# JTAG.net
KiCad netlist of a schematic drawn in Altium Designer
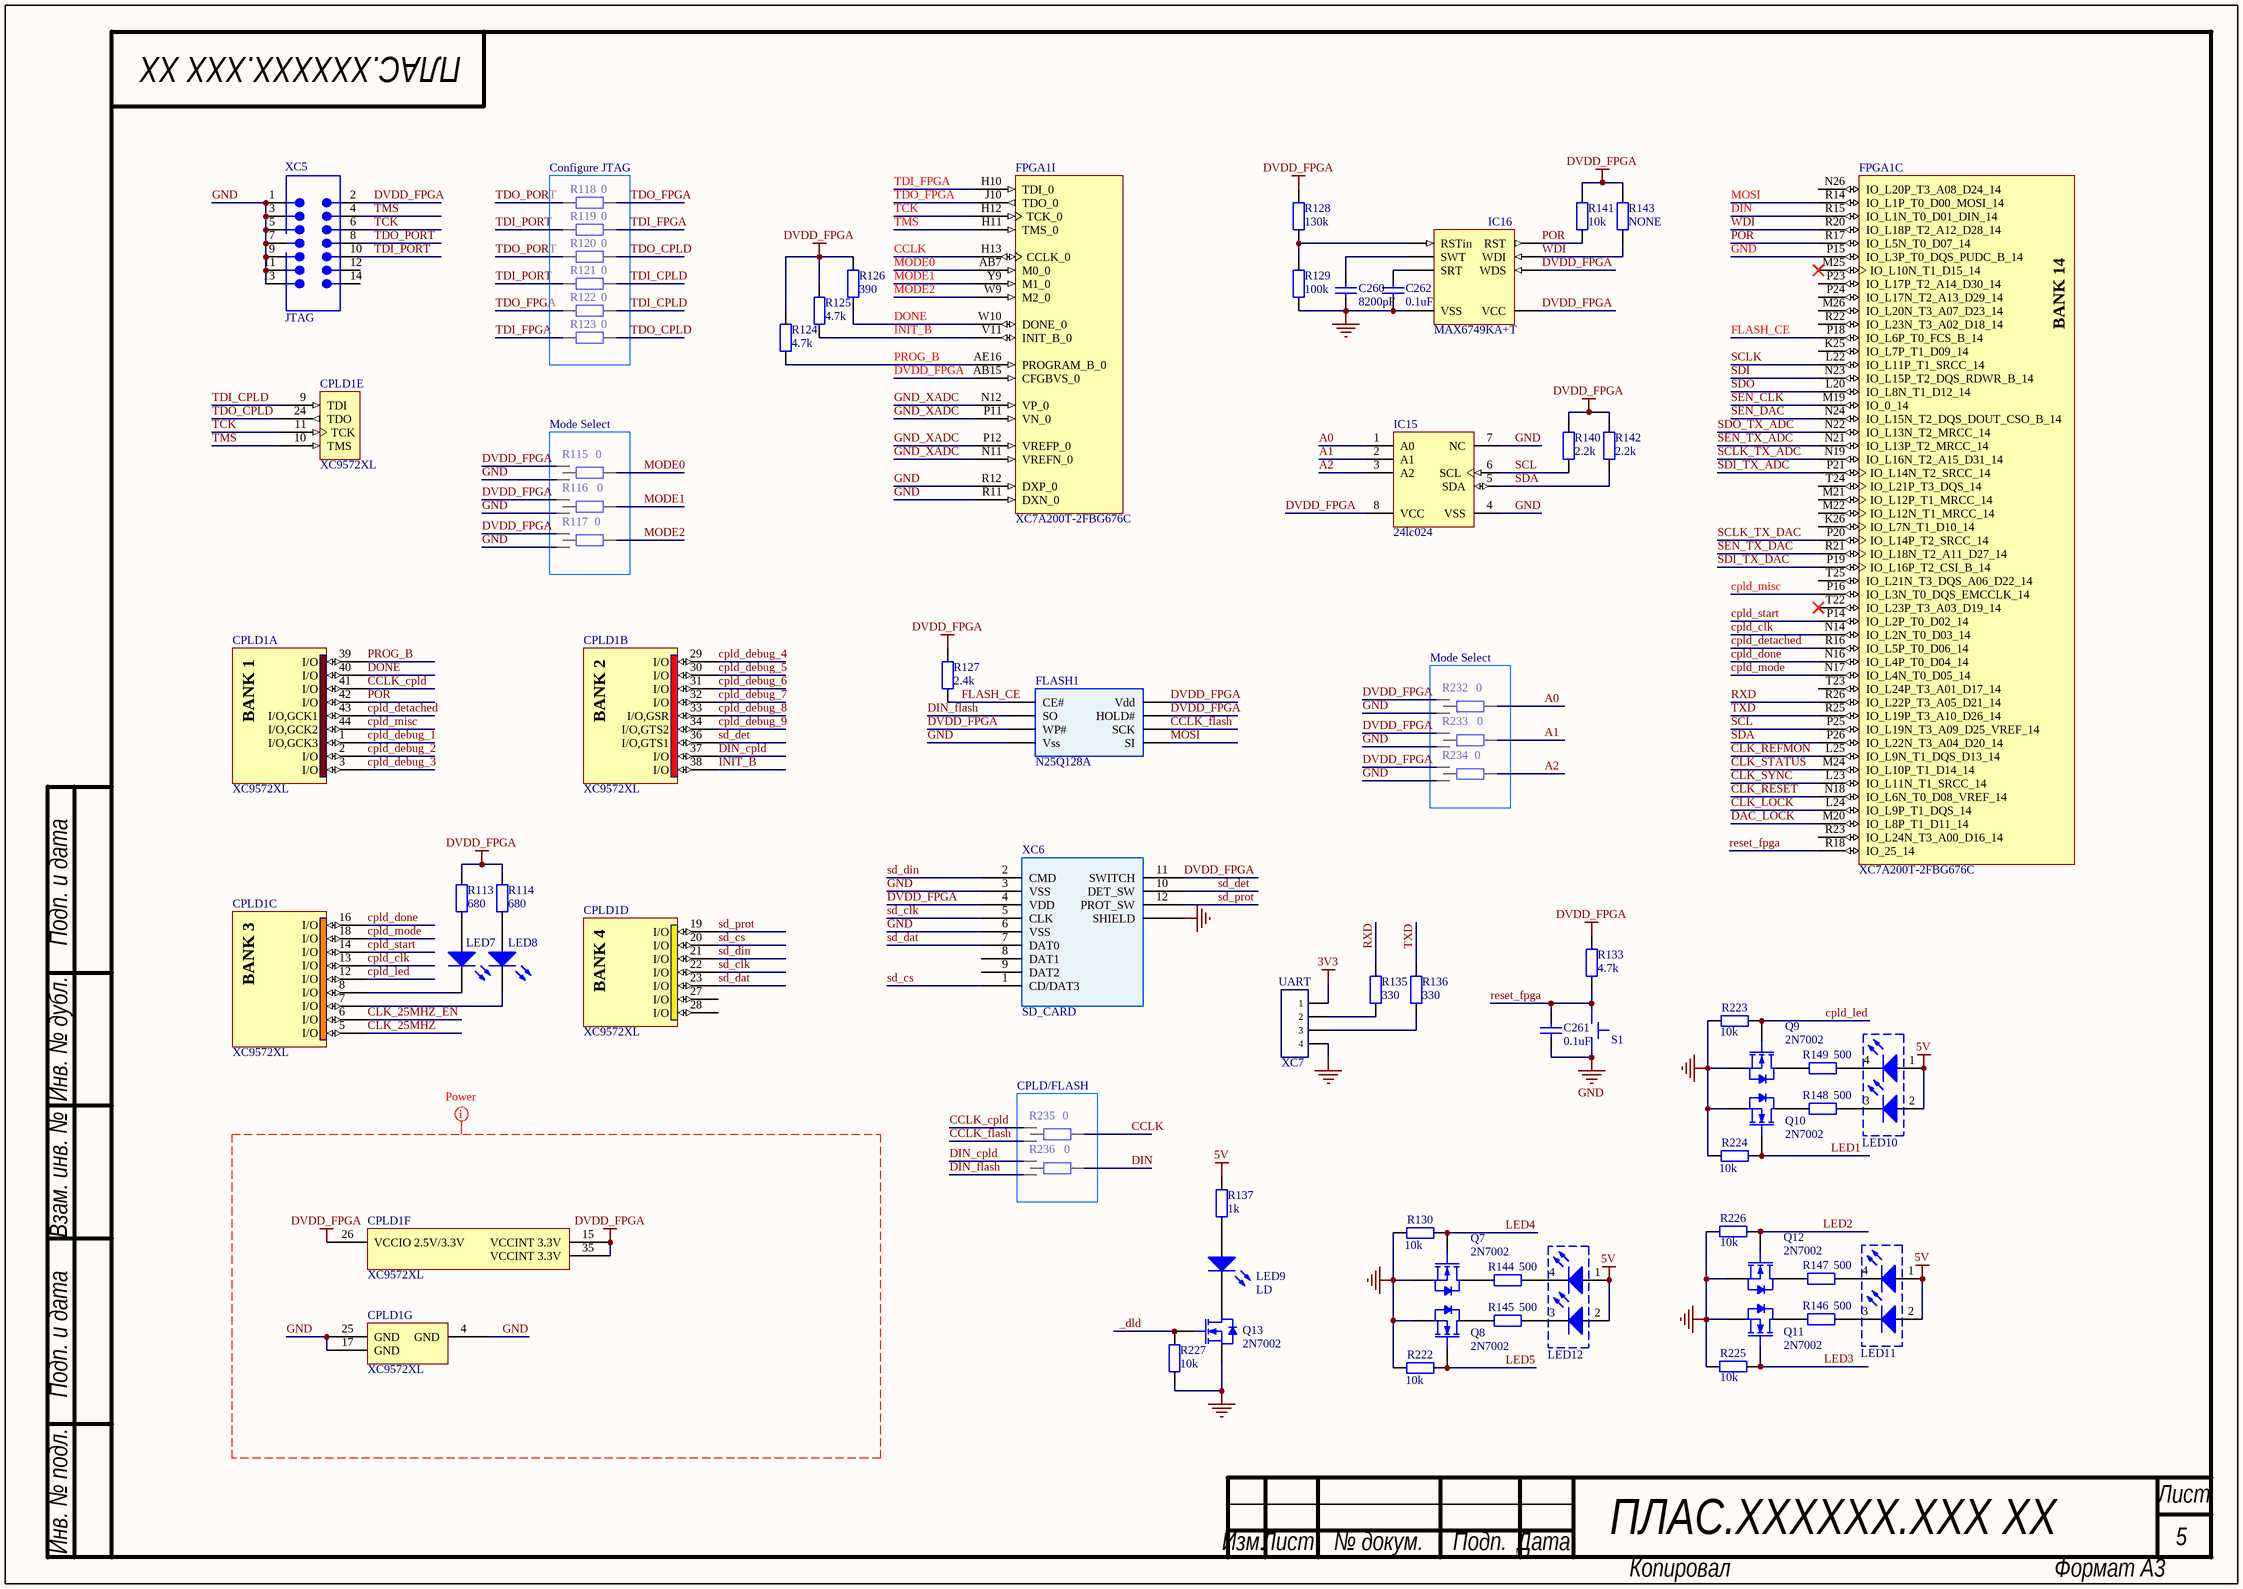
[diagram p0: JTAG.SchDoc]

(export (version "E")
  (design (tool "Eeschema 10.0.6"))
  (components
    (comp (ref "C260")
      (value "8200pF")
      (footprint "C0603")
      (description "Cer Cap Small")
      (fields (field (name "MANUFACTURER") "Murata") (field (name "VOLTAGE") "50V"))
      (libsource (lib "") (part "Cer Cap_1"))
    )
    (comp (ref "C261")
      (value "0.1uF")
      (footprint "C0603")
      (description "Cer Cap Small")
      (fields (field (name "MANUFACTURER") "Murata") (field (name "VOLTAGE") "16V"))
      (libsource (lib "USRP2_Clone") (part "Cer Cap"))
    )
    (comp (ref "C262")
      (value "0.1uF")
      (footprint "C0603")
      (description "Cer Cap Small")
      (fields (field (name "MANUFACTURER") "Murata") (field (name "VOLTAGE") "16V"))
      (libsource (lib "") (part "Cer Cap_1"))
    )
    (comp (ref "CPLD1")
      (value "XC9572XL")
      (footprint "VQFP44")
      (fields (field (name "VOLTAGE") "3.3 V"))
      (libsource (lib "USRP2_Clone") (part "XC9572XL-10VQ44C"))
    )
    (comp (ref "FLASH1")
      (value "N25Q128A")
      (footprint "SOIC8-W")
      (description "SPI Flash")
      (fields (field (name "VOLTAGE") "2.7-3.6V") (field (name "MANUFACTURER") "Micron Technology"))
      (libsource (lib "USRP2_Clone") (part "SST25VF016B-xx-xx-S2Ax"))
    )
    (comp (ref "FPGA1")
      (value "XC7A200T-2FBG676C")
      (footprint "FGG676")
      (description "Artix-7 FPGA, 400 User I/Os, 8 GTP, 676-Ball BGA, Speed Grade 2, Commercial Grade, Pb-Free")
      (fields (field (name "GENERIC PART NUMBER") "XC7A200T") (field (name "MANUFACTURER") "Xilinx"))
      (libsource (lib "USRP2_Clone") (part "XC7A200T-2FBG676C"))
    )
    (comp (ref "IC15")
      (value "24lc024")
      (footprint "SOIC_SN8")
      (description "I2C EEPROM")
      (fields (field (name "VOLTAGE") "2.5-5.5V") (field (name "MANUFACTURER") "Microchip"))
      (libsource (lib "USRP2_Clone") (part "24lc024"))
    )
    (comp (ref "IC16")
      (value "MAX6749KA+T")
      (footprint "SOT-23-8")
      (description "uC Reset Circuits")
      (fields (field (name "VOLTAGE") "1.0-5.5V") (field (name "MANUFACTURER") "Maxim"))
      (libsource (lib "USRP2_Clone") (part "MAX6749KA+T"))
    )
    (comp (ref "LED7")
      (value "LED")
      (footprint "LED_0402_Blue")
      (description "Typical RED, GREEN, YELLOW, AMBER GaAs LED")
      (fields (field (name "MANUFACTURER") "Kingbright"))
      (libsource (lib "USRP2_Clone") (part "LED"))
    )
    (comp (ref "LED8")
      (value "LED")
      (footprint "LED_0402_Blue")
      (description "Typical RED, GREEN, YELLOW, AMBER GaAs LED")
      (fields (field (name "MANUFACTURER") "Kingbright"))
      (libsource (lib "USRP2_Clone") (part "LED"))
    )
    (comp (ref "LED9")
      (value "LD")
      (footprint "LED_0402_Blue")
      (description "Typical RED, GREEN, YELLOW, AMBER GaAs LED")
      (fields (field (name "MANUFACTURER") "Kingbright"))
      (libsource (lib "USRP2_Clone") (part "LED"))
    )
    (comp (ref "LED10")
      (value "Green")
      (footprint "LED_PACK")
      (description "LED Pack For Front Panel")
      (fields (field (name "MANUFACTURER") "Kingbright"))
      (libsource (lib "USRP2_Clone") (part "LED_PACK"))
    )
    (comp (ref "LED11")
      (value "Green")
      (footprint "LED_PACK")
      (description "LED Pack For Front Panel")
      (fields (field (name "MANUFACTURER") "Kingbright"))
      (libsource (lib "USRP2_Clone") (part "LED_PACK"))
    )
    (comp (ref "LED12")
      (value "Green")
      (footprint "LED_PACK")
      (description "LED Pack For Front Panel")
      (fields (field (name "MANUFACTURER") "Kingbright"))
      (libsource (lib "USRP2_Clone") (part "LED_PACK"))
    )
    (comp (ref "Q7")
      (value "2N7002")
      (footprint "SOT-23")
      (description "N-Channel MOSFET 2N7002")
      (fields (field (name "VOLTAGE") "60V"))
      (libsource (lib "USRP2_Clone") (part "2N7002"))
    )
    (comp (ref "Q8")
      (value "2N7002")
      (footprint "SOT-23")
      (description "N-Channel MOSFET 2N7002")
      (fields (field (name "VOLTAGE") "60V"))
      (libsource (lib "USRP2_Clone") (part "2N7002"))
    )
    (comp (ref "Q9")
      (value "2N7002")
      (footprint "SOT-23")
      (description "N-Channel MOSFET 2N7002")
      (fields (field (name "VOLTAGE") "60V"))
      (libsource (lib "USRP2_Clone") (part "2N7002"))
    )
    (comp (ref "Q10")
      (value "2N7002")
      (footprint "SOT-23")
      (description "N-Channel MOSFET 2N7002")
      (fields (field (name "VOLTAGE") "60V"))
      (libsource (lib "USRP2_Clone") (part "2N7002"))
    )
    (comp (ref "Q11")
      (value "2N7002")
      (footprint "SOT-23")
      (description "N-Channel MOSFET 2N7002")
      (fields (field (name "VOLTAGE") "60V"))
      (libsource (lib "USRP2_Clone") (part "2N7002"))
    )
    (comp (ref "Q12")
      (value "2N7002")
      (footprint "SOT-23")
      (description "N-Channel MOSFET 2N7002")
      (fields (field (name "VOLTAGE") "60V"))
      (libsource (lib "USRP2_Clone") (part "2N7002"))
    )
    (comp (ref "Q13")
      (value "2N7002")
      (footprint "SOT-23")
      (description "N-Channel MOSFET 2N7002")
      (fields (field (name "VOLTAGE") "60V"))
      (libsource (lib "USRP2_Clone") (part "2N7002"))
    )
    (comp (ref "R113")
      (value "680")
      (footprint "R0402")
      (description "Resistor")
      (fields (field (name "TOLERANCE") "5%") (field (name "POWER") "0.062 Wt"))
      (libsource (lib "") (part "Res_2"))
    )
    (comp (ref "R114")
      (value "680")
      (footprint "R0402")
      (description "Resistor")
      (fields (field (name "TOLERANCE") "5%") (field (name "POWER") "0.062 Wt"))
      (libsource (lib "") (part "Res_2"))
    )
    (comp (ref "R115")
      (value "0")
      (footprint "R0402_Switch")
      (description "Resistor")
      (fields (field (name "TOLERANCE") "5%") (field (name "POWER") "0.062 Wt"))
      (libsource (lib "USRP2_Clone") (part "Res_Switch"))
    )
    (comp (ref "R116")
      (value "0")
      (footprint "R0402_Switch")
      (description "Resistor")
      (fields (field (name "TOLERANCE") "5%") (field (name "POWER") "0.062 Wt"))
      (libsource (lib "USRP2_Clone") (part "Res_Switch"))
    )
    (comp (ref "R117")
      (value "0")
      (footprint "R0402_Switch")
      (description "Resistor")
      (fields (field (name "TOLERANCE") "5%") (field (name "POWER") "0.062 Wt"))
      (libsource (lib "USRP2_Clone") (part "Res_Switch"))
    )
    (comp (ref "R118")
      (value "0")
      (footprint "R0402")
      (description "Resistor")
      (fields (field (name "TOLERANCE") "5%") (field (name "POWER") "0.062 Wt"))
      (libsource (lib "") (part "Res_1"))
    )
    (comp (ref "R119")
      (value "0")
      (footprint "R0402")
      (description "Resistor")
      (fields (field (name "TOLERANCE") "5%") (field (name "POWER") "0.062 Wt"))
      (libsource (lib "") (part "Res_1"))
    )
    (comp (ref "R120")
      (value "0")
      (footprint "R0402")
      (description "Resistor")
      (fields (field (name "TOLERANCE") "5%") (field (name "POWER") "0.062 Wt"))
      (libsource (lib "") (part "Res_1"))
    )
    (comp (ref "R121")
      (value "0")
      (footprint "R0402")
      (description "Resistor")
      (fields (field (name "TOLERANCE") "5%") (field (name "POWER") "0.062 Wt"))
      (libsource (lib "") (part "Res_1"))
    )
    (comp (ref "R122")
      (value "0")
      (footprint "R0402")
      (description "Resistor")
      (fields (field (name "TOLERANCE") "5%") (field (name "POWER") "0.062 Wt"))
      (libsource (lib "") (part "Res_1"))
    )
    (comp (ref "R123")
      (value "0")
      (footprint "R0402")
      (description "Resistor")
      (fields (field (name "TOLERANCE") "5%") (field (name "POWER") "0.062 Wt"))
      (libsource (lib "") (part "Res_1"))
    )
    (comp (ref "R124")
      (value "4.7k")
      (footprint "R0402")
      (description "Resistor")
      (fields (field (name "TOLERANCE") "5%") (field (name "POWER") "0.062 Wt"))
      (libsource (lib "USRP2_Clone") (part "Res"))
    )
    (comp (ref "R125")
      (value "4.7k")
      (footprint "R0402")
      (description "Resistor")
      (fields (field (name "TOLERANCE") "5%") (field (name "POWER") "0.062 Wt"))
      (libsource (lib "") (part "Res_6"))
    )
    (comp (ref "R126")
      (value "390")
      (footprint "R0402")
      (description "Resistor")
      (fields (field (name "TOLERANCE") "5%") (field (name "POWER") "0.062 Wt"))
      (libsource (lib "USRP2_Clone") (part "Res"))
    )
    (comp (ref "R127")
      (value "2.4k")
      (footprint "R0402")
      (description "Resistor")
      (fields (field (name "TOLERANCE") "5%") (field (name "POWER") "0.062 Wt"))
      (libsource (lib "USRP2_Clone") (part "Res"))
    )
    (comp (ref "R128")
      (value "130k")
      (footprint "R0402")
      (description "Resistor")
      (fields (field (name "TOLERANCE") "5%") (field (name "POWER") "0.062 Wt"))
      (libsource (lib "") (part "Res_2"))
    )
    (comp (ref "R129")
      (value "100k")
      (footprint "R0402")
      (description "Resistor")
      (fields (field (name "TOLERANCE") "5%") (field (name "POWER") "0.062 Wt"))
      (libsource (lib "") (part "Res_2"))
    )
    (comp (ref "R130")
      (value "10k")
      (footprint "R0402")
      (description "Resistor")
      (fields (field (name "TOLERANCE") "5%") (field (name "POWER") "0.062 Wt"))
      (libsource (lib "") (part "Res_3"))
    )
    (comp (ref "R133")
      (value "4.7k")
      (footprint "R0402")
      (description "Resistor")
      (fields (field (name "TOLERANCE") "5%") (field (name "POWER") "0.062 Wt"))
      (libsource (lib "") (part "Res_2"))
    )
    (comp (ref "R135")
      (value "330")
      (footprint "R0402")
      (description "Resistor")
      (fields (field (name "TOLERANCE") "5%") (field (name "POWER") "0.062 Wt"))
      (libsource (lib "") (part "Res_4"))
    )
    (comp (ref "R136")
      (value "330")
      (footprint "R0402")
      (description "Resistor")
      (fields (field (name "TOLERANCE") "5%") (field (name "POWER") "0.062 Wt"))
      (libsource (lib "") (part "Res_4"))
    )
    (comp (ref "R137")
      (value "1k")
      (footprint "R0402")
      (description "Resistor")
      (fields (field (name "TOLERANCE") "5%") (field (name "POWER") "0.062 Wt"))
      (libsource (lib "") (part "Res_2"))
    )
    (comp (ref "R140")
      (value "2.2k")
      (footprint "R0402")
      (description "Resistor")
      (fields (field (name "TOLERANCE") "5%") (field (name "POWER") "0.062 Wt"))
      (libsource (lib "") (part "Res_2"))
    )
    (comp (ref "R141")
      (value "10k")
      (footprint "R0402")
      (description "Resistor")
      (fields (field (name "TOLERANCE") "5%") (field (name "POWER") "0.062 Wt"))
      (libsource (lib "") (part "Res_2"))
    )
    (comp (ref "R142")
      (value "2.2k")
      (footprint "R0402")
      (description "Resistor")
      (fields (field (name "TOLERANCE") "5%") (field (name "POWER") "0.062 Wt"))
      (libsource (lib "") (part "Res_2"))
    )
    (comp (ref "R143")
      (value "NONE")
      (footprint "R0402")
      (description "Resistor")
      (fields (field (name "TOLERANCE") "5%") (field (name "POWER") "0.062 Wt"))
      (libsource (lib "") (part "Res_2"))
    )
    (comp (ref "R144")
      (value "500")
      (footprint "R0402")
      (description "Resistor")
      (fields (field (name "TOLERANCE") "5%") (field (name "POWER") "0.062 Wt"))
      (libsource (lib "") (part "Res_5"))
    )
    (comp (ref "R145")
      (value "500")
      (footprint "R0402")
      (description "Resistor")
      (fields (field (name "TOLERANCE") "5%") (field (name "POWER") "0.062 Wt"))
      (libsource (lib "") (part "Res_5"))
    )
    (comp (ref "R146")
      (value "500")
      (footprint "R0402")
      (description "Resistor")
      (fields (field (name "TOLERANCE") "5%") (field (name "POWER") "0.062 Wt"))
      (libsource (lib "") (part "Res_2"))
    )
    (comp (ref "R147")
      (value "500")
      (footprint "R0402")
      (description "Resistor")
      (fields (field (name "TOLERANCE") "5%") (field (name "POWER") "0.062 Wt"))
      (libsource (lib "") (part "Res_2"))
    )
    (comp (ref "R148")
      (value "500")
      (footprint "R0402")
      (description "Resistor")
      (fields (field (name "TOLERANCE") "5%") (field (name "POWER") "0.062 Wt"))
      (libsource (lib "") (part "Res_1"))
    )
    (comp (ref "R149")
      (value "500")
      (footprint "R0402")
      (description "Resistor")
      (fields (field (name "TOLERANCE") "5%") (field (name "POWER") "0.062 Wt"))
      (libsource (lib "") (part "Res_5"))
    )
    (comp (ref "R222")
      (value "10k")
      (footprint "R0402")
      (description "Resistor")
      (fields (field (name "TOLERANCE") "5%") (field (name "POWER") "0.062 Wt"))
      (libsource (lib "") (part "Res_3"))
    )
    (comp (ref "R223")
      (value "10k")
      (footprint "R0402")
      (description "Resistor")
      (fields (field (name "TOLERANCE") "5%") (field (name "POWER") "0.062 Wt"))
      (libsource (lib "") (part "Res_3"))
    )
    (comp (ref "R224")
      (value "10k")
      (footprint "R0402")
      (description "Resistor")
      (fields (field (name "TOLERANCE") "5%") (field (name "POWER") "0.062 Wt"))
      (libsource (lib "") (part "Res_3"))
    )
    (comp (ref "R225")
      (value "10k")
      (footprint "R0402")
      (description "Resistor")
      (fields (field (name "TOLERANCE") "5%") (field (name "POWER") "0.062 Wt"))
      (libsource (lib "") (part "Res_4"))
    )
    (comp (ref "R226")
      (value "10k")
      (footprint "R0402")
      (description "Resistor")
      (fields (field (name "TOLERANCE") "5%") (field (name "POWER") "0.062 Wt"))
      (libsource (lib "") (part "Res_4"))
    )
    (comp (ref "R227")
      (value "10k")
      (footprint "R0402")
      (description "Resistor")
      (fields (field (name "TOLERANCE") "5%") (field (name "POWER") "0.062 Wt"))
      (libsource (lib "") (part "Res_2"))
    )
    (comp (ref "R232")
      (value "0")
      (footprint "R0402_Switch")
      (description "Resistor")
      (fields (field (name "TOLERANCE") "5%") (field (name "POWER") "0.062 Wt"))
      (libsource (lib "USRP2_Clone") (part "Res_Switch"))
    )
    (comp (ref "R233")
      (value "0")
      (footprint "R0402_Switch")
      (description "Resistor")
      (fields (field (name "TOLERANCE") "5%") (field (name "POWER") "0.062 Wt"))
      (libsource (lib "USRP2_Clone") (part "Res_Switch"))
    )
    (comp (ref "R234")
      (value "0")
      (footprint "R0402_Switch")
      (description "Resistor")
      (fields (field (name "TOLERANCE") "5%") (field (name "POWER") "0.062 Wt"))
      (libsource (lib "USRP2_Clone") (part "Res_Switch"))
    )
    (comp (ref "R235")
      (value "0")
      (footprint "R0402_Switch")
      (description "Resistor")
      (fields (field (name "TOLERANCE") "5%") (field (name "POWER") "0.062 Wt"))
      (libsource (lib "USRP2_Clone") (part "Res_Switch"))
    )
    (comp (ref "R236")
      (value "0")
      (footprint "R0402_Switch")
      (description "Resistor")
      (fields (field (name "TOLERANCE") "5%") (field (name "POWER") "0.062 Wt"))
      (libsource (lib "USRP2_Clone") (part "Res_Switch"))
    )
    (comp (ref "S1")
      (value "RST_FPGA")
      (footprint "B3FS-1000")
      (fields (field (name "MANUFACTURER") "Omron") (field (name "VOLTAGE") "24V"))
      (libsource (lib "USRP2_Clone") (part "Push Button"))
    )
    (comp (ref "XC5")
      (value "JTAG")
      (footprint "JTAG Mail")
      (description "Male Header JTAG")
      (fields (field (name "MANUFACTURER") "CNC Tech"))
      (libsource (lib "USRP2_Clone") (part "JTAG Male"))
    )
    (comp (ref "XC6")
      (value "SD_CARD")
      (footprint "SD_Card")
      (fields (field (name "MANUFACTURER") "Tyco Electronics"))
      (libsource (lib "USRP2_Clone") (part "SD_Card"))
    )
    (comp (ref "XC7")
      (value "UART")
      (footprint "Right Angle Male Header")
      (description "4-Way Angle PCB Header")
      (libsource (lib "USRP2_Clone") (part "4-Way Header"))
    )
  )
  (nets
    (net (code "1") (name "/A0") (class "Default")
      (node (ref "IC15") (pin "1") (pinfunction "A0_1") (pintype "passive"))
      (node (ref "R232") (pin "2") (pinfunction "2_2") (pintype "passive"))
    )
    (net (code "2") (name "/A1") (class "Default")
      (node (ref "IC15") (pin "2") (pinfunction "A1_2") (pintype "passive"))
      (node (ref "R233") (pin "2") (pinfunction "2_2") (pintype "passive"))
    )
    (net (code "3") (name "/A2") (class "Default")
      (node (ref "IC15") (pin "3") (pinfunction "A2_3") (pintype "passive"))
      (node (ref "R234") (pin "2") (pinfunction "2_2") (pintype "passive"))
    )
    (net (code "4") (name "/CCLK") (class "Default")
      (node (ref "FPGA1") (pin "H13") (pinfunction "CCLK_0_H13") (pintype "bidirectional"))
      (node (ref "R235") (pin "2") (pinfunction "2_2") (pintype "passive"))
    )
    (net (code "5") (name "/CCLK_cpld") (class "Default")
      (node (ref "CPLD1") (pin "41") (pinfunction "I/O_41") (pintype "bidirectional"))
      (node (ref "R235") (pin "1") (pinfunction "1_1") (pintype "passive"))
    )
    (net (code "6") (name "/CCLK_flash") (class "Default")
      (node (ref "FLASH1") (pin "6") (pinfunction "SCK_6") (pintype "passive"))
      (node (ref "R235") (pin "3") (pinfunction "3_3") (pintype "passive"))
    )
    (net (code "7") (name "/CLK_25MHZ") (class "Default")
      (node (ref "CPLD1") (pin "5") (pinfunction "I/O_5") (pintype "bidirectional"))
    )
    (net (code "8") (name "/CLK_25MHZ_EN") (class "Default")
      (node (ref "CPLD1") (pin "6") (pinfunction "I/O_6") (pintype "bidirectional"))
    )
    (net (code "9") (name "/CLK_LOCK") (class "Default")
      (node (ref "FPGA1") (pin "L24") (pinfunction "IO_L9P_T1_DQS_14_L24") (pintype "bidirectional"))
    )
    (net (code "10") (name "/CLK_REFMON") (class "Default")
      (node (ref "FPGA1") (pin "L25") (pinfunction "IO_L9N_T1_DQS_D13_14_L25") (pintype "bidirectional"))
    )
    (net (code "11") (name "/CLK_RESET") (class "Default")
      (node (ref "FPGA1") (pin "N18") (pinfunction "IO_L6N_T0_D08_VREF_14_N18") (pintype "bidirectional"))
    )
    (net (code "12") (name "/CLK_STATUS") (class "Default")
      (node (ref "FPGA1") (pin "M24") (pinfunction "IO_L10P_T1_D14_14_M24") (pintype "bidirectional"))
    )
    (net (code "13") (name "/CLK_SYNC") (class "Default")
      (node (ref "FPGA1") (pin "L23") (pinfunction "IO_L11N_T1_SRCC_14_L23") (pintype "bidirectional"))
    )
    (net (code "14") (name "/DAC_LOCK") (class "Default")
      (node (ref "FPGA1") (pin "M20") (pinfunction "IO_L8P_T1_D11_14_M20") (pintype "bidirectional"))
    )
    (net (code "15") (name "/DIN") (class "Default")
      (node (ref "FPGA1") (pin "R15") (pinfunction "IO_L1N_T0_D01_DIN_14_R15") (pintype "bidirectional"))
      (node (ref "R236") (pin "2") (pinfunction "2_2") (pintype "passive"))
    )
    (net (code "16") (name "/DIN_cpld") (class "Default")
      (node (ref "CPLD1") (pin "37") (pinfunction "I/O_37") (pintype "bidirectional"))
      (node (ref "R236") (pin "1") (pinfunction "1_1") (pintype "passive"))
    )
    (net (code "17") (name "/DIN_flash") (class "Default")
      (node (ref "FLASH1") (pin "2") (pinfunction "SO_2") (pintype "passive"))
      (node (ref "R236") (pin "3") (pinfunction "3_3") (pintype "passive"))
    )
    (net (code "18") (name "/DONE") (class "Default")
      (node (ref "CPLD1") (pin "40") (pinfunction "I/O_40") (pintype "bidirectional"))
      (node (ref "FPGA1") (pin "W10") (pinfunction "DONE_0_W10") (pintype "bidirectional"))
      (node (ref "R126") (pin "2") (pinfunction "2_2") (pintype "passive"))
    )
    (net (code "19") (name "/FLASH_CE") (class "Default")
      (node (ref "FLASH1") (pin "1") (pinfunction "CE#_1") (pintype "passive"))
      (node (ref "FPGA1") (pin "P18") (pinfunction "IO_L6P_T0_FCS_B_14_P18") (pintype "bidirectional"))
      (node (ref "R127") (pin "2") (pinfunction "2_2") (pintype "passive"))
    )
    (net (code "20") (name "/GND_XADC") (class "Default")
      (node (ref "FPGA1") (pin "N11") (pinfunction "VREFN_0_N11") (pintype "input"))
      (node (ref "FPGA1") (pin "N12") (pinfunction "VP_0_N12") (pintype "input"))
      (node (ref "FPGA1") (pin "P11") (pinfunction "VN_0_P11") (pintype "input"))
      (node (ref "FPGA1") (pin "P12") (pinfunction "VREFP_0_P12") (pintype "input"))
    )
    (net (code "21") (name "/INIT_B") (class "Default")
      (node (ref "CPLD1") (pin "38") (pinfunction "I/O_38") (pintype "bidirectional"))
      (node (ref "FPGA1") (pin "V11") (pinfunction "INIT_B_0_V11") (pintype "bidirectional"))
      (node (ref "R125") (pin "1") (pinfunction "1_1") (pintype "passive"))
    )
    (net (code "22") (name "/LED1") (class "Default")
      (node (ref "Q10") (pin "1") (pinfunction "G_1") (pintype "passive"))
      (node (ref "R224") (pin "1") (pinfunction "1_1") (pintype "passive"))
    )
    (net (code "23") (name "/LED2") (class "Default")
      (node (ref "Q12") (pin "1") (pinfunction "G_1") (pintype "passive"))
      (node (ref "R226") (pin "1") (pinfunction "1_1") (pintype "passive"))
    )
    (net (code "24") (name "/LED3") (class "Default")
      (node (ref "Q11") (pin "1") (pinfunction "G_1") (pintype "passive"))
      (node (ref "R225") (pin "1") (pinfunction "1_1") (pintype "passive"))
    )
    (net (code "25") (name "/LED4") (class "Default")
      (node (ref "Q7") (pin "1") (pinfunction "G_1") (pintype "passive"))
      (node (ref "R130") (pin "1") (pinfunction "1_1") (pintype "passive"))
    )
    (net (code "26") (name "/LED5") (class "Default")
      (node (ref "Q8") (pin "1") (pinfunction "G_1") (pintype "passive"))
      (node (ref "R222") (pin "1") (pinfunction "1_1") (pintype "passive"))
    )
    (net (code "27") (name "/MODE0") (class "Default")
      (node (ref "FPGA1") (pin "AB7") (pinfunction "M0_0_AB7") (pintype "input"))
      (node (ref "R115") (pin "2") (pinfunction "2_2") (pintype "passive"))
    )
    (net (code "28") (name "/MODE1") (class "Default")
      (node (ref "FPGA1") (pin "Y9") (pinfunction "M1_0_Y9") (pintype "input"))
      (node (ref "R116") (pin "2") (pinfunction "2_2") (pintype "passive"))
    )
    (net (code "29") (name "/MODE2") (class "Default")
      (node (ref "FPGA1") (pin "W9") (pinfunction "M2_0_W9") (pintype "input"))
      (node (ref "R117") (pin "2") (pinfunction "2_2") (pintype "passive"))
    )
    (net (code "30") (name "/MOSI") (class "Default")
      (node (ref "FLASH1") (pin "5") (pinfunction "SI_5") (pintype "passive"))
      (node (ref "FPGA1") (pin "R14") (pinfunction "IO_L1P_T0_D00_MOSI_14_R14") (pintype "bidirectional"))
    )
    (net (code "31") (name "/POR") (class "Default")
      (node (ref "CPLD1") (pin "42") (pinfunction "I/O_42") (pintype "bidirectional"))
      (node (ref "FPGA1") (pin "R17") (pinfunction "IO_L5N_T0_D07_14_R17") (pintype "bidirectional"))
      (node (ref "IC16") (pin "7") (pinfunction "RST_7") (pintype "output"))
      (node (ref "R141") (pin "1") (pinfunction "1_1") (pintype "passive"))
    )
    (net (code "32") (name "/PROG_B") (class "Default")
      (node (ref "CPLD1") (pin "39") (pinfunction "I/O_39") (pintype "bidirectional"))
      (node (ref "FPGA1") (pin "AE16") (pinfunction "PROGRAM_B_0_AE16") (pintype "input"))
      (node (ref "R124") (pin "2") (pinfunction "2_2") (pintype "passive"))
    )
    (net (code "33") (name "/RXD") (class "Default")
      (node (ref "FPGA1") (pin "R26") (pinfunction "IO_L22P_T3_A05_D21_14_R26") (pintype "bidirectional"))
      (node (ref "R135") (pin "1") (pinfunction "1_1") (pintype "passive"))
    )
    (net (code "34") (name "/SCL") (class "Default")
      (node (ref "FPGA1") (pin "P25") (pinfunction "IO_L19N_T3_A09_D25_VREF_14_P25") (pintype "bidirectional"))
      (node (ref "IC15") (pin "6") (pinfunction "SCL_6") (pintype "input"))
      (node (ref "R140") (pin "1") (pinfunction "1_1") (pintype "passive"))
    )
    (net (code "35") (name "/SCLK") (class "Default")
      (node (ref "FPGA1") (pin "L22") (pinfunction "IO_L11P_T1_SRCC_14_L22") (pintype "bidirectional"))
    )
    (net (code "36") (name "/SCLK_TX_ADC") (class "Default")
      (node (ref "FPGA1") (pin "N19") (pinfunction "IO_L16N_T2_A15_D31_14_N19") (pintype "bidirectional"))
    )
    (net (code "37") (name "/SCLK_TX_DAC") (class "Default")
      (node (ref "FPGA1") (pin "P20") (pinfunction "IO_L14P_T2_SRCC_14_P20") (pintype "bidirectional"))
    )
    (net (code "38") (name "/SDA") (class "Default")
      (node (ref "FPGA1") (pin "P26") (pinfunction "IO_L22N_T3_A04_D20_14_P26") (pintype "bidirectional"))
      (node (ref "IC15") (pin "5") (pinfunction "SDA_5") (pintype "bidirectional"))
      (node (ref "R142") (pin "1") (pinfunction "1_1") (pintype "passive"))
    )
    (net (code "39") (name "/SDI") (class "Default")
      (node (ref "FPGA1") (pin "N23") (pinfunction "IO_L15P_T2_DQS_RDWR_B_14_N23") (pintype "bidirectional"))
    )
    (net (code "40") (name "/SDI_TX_ADC") (class "Default")
      (node (ref "FPGA1") (pin "P21") (pinfunction "IO_L14N_T2_SRCC_14_P21") (pintype "bidirectional"))
    )
    (net (code "41") (name "/SDI_TX_DAC") (class "Default")
      (node (ref "FPGA1") (pin "P19") (pinfunction "IO_L16P_T2_CSI_B_14_P19") (pintype "bidirectional"))
    )
    (net (code "42") (name "/SDO") (class "Default")
      (node (ref "FPGA1") (pin "L20") (pinfunction "IO_L8N_T1_D12_14_L20") (pintype "bidirectional"))
    )
    (net (code "43") (name "/SDO_TX_ADC") (class "Default")
      (node (ref "FPGA1") (pin "N22") (pinfunction "IO_L13N_T2_MRCC_14_N22") (pintype "bidirectional"))
    )
    (net (code "44") (name "/SEN_CLK") (class "Default")
      (node (ref "FPGA1") (pin "M19") (pinfunction "IO_0_14_M19") (pintype "bidirectional"))
    )
    (net (code "45") (name "/SEN_DAC") (class "Default")
      (node (ref "FPGA1") (pin "N24") (pinfunction "IO_L15N_T2_DQS_DOUT_CSO_B_14_N24") (pintype "bidirectional"))
    )
    (net (code "46") (name "/SEN_TX_ADC") (class "Default")
      (node (ref "FPGA1") (pin "N21") (pinfunction "IO_L13P_T2_MRCC_14_N21") (pintype "bidirectional"))
    )
    (net (code "47") (name "/SEN_TX_DAC") (class "Default")
      (node (ref "FPGA1") (pin "R21") (pinfunction "IO_L18N_T2_A11_D27_14_R21") (pintype "bidirectional"))
    )
    (net (code "48") (name "/TCK") (class "Default")
      (node (ref "CPLD1") (pin "11") (pinfunction "TCK_11") (pintype "input"))
      (node (ref "FPGA1") (pin "H12") (pinfunction "TCK_0_H12") (pintype "input"))
      (node (ref "XC5") (pin "6") (pinfunction "TCK_6") (pintype "passive"))
    )
    (net (code "49") (name "/TDI_CPLD") (class "Default")
      (node (ref "CPLD1") (pin "9") (pinfunction "TDI_9") (pintype "input"))
      (node (ref "R121") (pin "2") (pinfunction "2_2") (pintype "passive"))
      (node (ref "R122") (pin "2") (pinfunction "2_2") (pintype "passive"))
    )
    (net (code "50") (name "/TDI_FPGA") (class "Default")
      (node (ref "FPGA1") (pin "H10") (pinfunction "TDI_0_H10") (pintype "input"))
      (node (ref "R119") (pin "2") (pinfunction "2_2") (pintype "passive"))
      (node (ref "R123") (pin "1") (pinfunction "1_1") (pintype "passive"))
    )
    (net (code "51") (name "/TDI_PORT") (class "Default")
      (node (ref "R119") (pin "1") (pinfunction "1_1") (pintype "passive"))
      (node (ref "R121") (pin "1") (pinfunction "1_1") (pintype "passive"))
      (node (ref "XC5") (pin "10") (pinfunction "TDI_10") (pintype "passive"))
    )
    (net (code "52") (name "/TDO_CPLD") (class "Default")
      (node (ref "CPLD1") (pin "24") (pinfunction "TDO_24") (pintype "output"))
      (node (ref "R120") (pin "2") (pinfunction "2_2") (pintype "passive"))
      (node (ref "R123") (pin "2") (pinfunction "2_2") (pintype "passive"))
    )
    (net (code "53") (name "/TDO_FPGA") (class "Default")
      (node (ref "FPGA1") (pin "J10") (pinfunction "TDO_0_J10") (pintype "output"))
      (node (ref "R118") (pin "2") (pinfunction "2_2") (pintype "passive"))
      (node (ref "R122") (pin "1") (pinfunction "1_1") (pintype "passive"))
    )
    (net (code "54") (name "/TDO_PORT") (class "Default")
      (node (ref "R118") (pin "1") (pinfunction "1_1") (pintype "passive"))
      (node (ref "R120") (pin "1") (pinfunction "1_1") (pintype "passive"))
      (node (ref "XC5") (pin "8") (pinfunction "TDO_8") (pintype "passive"))
    )
    (net (code "55") (name "/TMS") (class "Default")
      (node (ref "CPLD1") (pin "10") (pinfunction "TMS_10") (pintype "input"))
      (node (ref "FPGA1") (pin "H11") (pinfunction "TMS_0_H11") (pintype "input"))
      (node (ref "XC5") (pin "4") (pinfunction "TMS_4") (pintype "passive"))
    )
    (net (code "56") (name "/TXD") (class "Default")
      (node (ref "FPGA1") (pin "R25") (pinfunction "IO_L19P_T3_A10_D26_14_R25") (pintype "bidirectional"))
      (node (ref "R136") (pin "1") (pinfunction "1_1") (pintype "passive"))
    )
    (net (code "57") (name "/WDI") (class "Default")
      (node (ref "FPGA1") (pin "R20") (pinfunction "IO_L18P_T2_A12_D28_14_R20") (pintype "bidirectional"))
      (node (ref "IC16") (pin "6") (pinfunction "WDI_6") (pintype "input"))
      (node (ref "R143") (pin "1") (pinfunction "1_1") (pintype "passive"))
    )
    (net (code "58") (name "/_dld") (class "Default")
      (node (ref "Q13") (pin "1") (pinfunction "G_1") (pintype "passive"))
      (node (ref "R227") (pin "2") (pinfunction "2_2") (pintype "passive"))
    )
    (net (code "59") (name "/cpld_clk") (class "Default")
      (node (ref "CPLD1") (pin "13") (pinfunction "I/O_13") (pintype "bidirectional"))
      (node (ref "FPGA1") (pin "N14") (pinfunction "IO_L2N_T0_D03_14_N14") (pintype "bidirectional"))
    )
    (net (code "60") (name "/cpld_debug_1") (class "Default")
      (node (ref "CPLD1") (pin "1") (pinfunction "I/O,GCK3_1") (pintype "bidirectional"))
    )
    (net (code "61") (name "/cpld_debug_2") (class "Default")
      (node (ref "CPLD1") (pin "2") (pinfunction "I/O_2") (pintype "bidirectional"))
    )
    (net (code "62") (name "/cpld_debug_3") (class "Default")
      (node (ref "CPLD1") (pin "3") (pinfunction "I/O_3") (pintype "bidirectional"))
    )
    (net (code "63") (name "/cpld_debug_4") (class "Default")
      (node (ref "CPLD1") (pin "29") (pinfunction "I/O_29") (pintype "bidirectional"))
    )
    (net (code "64") (name "/cpld_debug_5") (class "Default")
      (node (ref "CPLD1") (pin "30") (pinfunction "I/O_30") (pintype "bidirectional"))
    )
    (net (code "65") (name "/cpld_debug_6") (class "Default")
      (node (ref "CPLD1") (pin "31") (pinfunction "I/O_31") (pintype "bidirectional"))
    )
    (net (code "66") (name "/cpld_debug_7") (class "Default")
      (node (ref "CPLD1") (pin "32") (pinfunction "I/O_32") (pintype "bidirectional"))
    )
    (net (code "67") (name "/cpld_debug_8") (class "Default")
      (node (ref "CPLD1") (pin "33") (pinfunction "I/O,GSR_33") (pintype "bidirectional"))
    )
    (net (code "68") (name "/cpld_debug_9") (class "Default")
      (node (ref "CPLD1") (pin "34") (pinfunction "I/O,GTS2_34") (pintype "bidirectional"))
    )
    (net (code "69") (name "/cpld_detached") (class "Default")
      (node (ref "CPLD1") (pin "43") (pinfunction "I/O,GCK1_43") (pintype "bidirectional"))
      (node (ref "FPGA1") (pin "R16") (pinfunction "IO_L5P_T0_D06_14_R16") (pintype "bidirectional"))
    )
    (net (code "70") (name "/cpld_done") (class "Default")
      (node (ref "CPLD1") (pin "16") (pinfunction "I/O_16") (pintype "bidirectional"))
      (node (ref "FPGA1") (pin "N16") (pinfunction "IO_L4P_T0_D04_14_N16") (pintype "bidirectional"))
    )
    (net (code "71") (name "/cpld_led") (class "Default")
      (node (ref "CPLD1") (pin "12") (pinfunction "I/O_12") (pintype "bidirectional"))
      (node (ref "Q9") (pin "1") (pinfunction "G_1") (pintype "passive"))
      (node (ref "R223") (pin "1") (pinfunction "1_1") (pintype "passive"))
    )
    (net (code "72") (name "/cpld_misc") (class "Default")
      (node (ref "CPLD1") (pin "44") (pinfunction "I/O,GCK2_44") (pintype "bidirectional"))
      (node (ref "FPGA1") (pin "P16") (pinfunction "IO_L3N_T0_DQS_EMCCLK_14_P16") (pintype "bidirectional"))
    )
    (net (code "73") (name "/cpld_mode") (class "Default")
      (node (ref "CPLD1") (pin "18") (pinfunction "I/O_18") (pintype "bidirectional"))
      (node (ref "FPGA1") (pin "N17") (pinfunction "IO_L4N_T0_D05_14_N17") (pintype "bidirectional"))
    )
    (net (code "74") (name "/cpld_start") (class "Default")
      (node (ref "CPLD1") (pin "14") (pinfunction "I/O_14") (pintype "bidirectional"))
      (node (ref "FPGA1") (pin "P14") (pinfunction "IO_L2P_T0_D02_14_P14") (pintype "bidirectional"))
    )
    (net (code "75") (name "/reset_fpga") (class "Default")
      (node (ref "C261") (pin "1") (pinfunction "1_1") (pintype "passive"))
      (node (ref "FPGA1") (pin "R18") (pinfunction "IO_25_14_R18") (pintype "bidirectional"))
      (node (ref "R133") (pin "1") (pinfunction "1_1") (pintype "passive"))
      (node (ref "S1") (pin "1") (pinfunction "1_1") (pintype "passive"))
    )
    (net (code "76") (name "/sd_clk") (class "Default")
      (node (ref "CPLD1") (pin "22") (pinfunction "I/O_22") (pintype "bidirectional"))
      (node (ref "XC6") (pin "5") (pinfunction "CLK_5") (pintype "passive"))
    )
    (net (code "77") (name "/sd_cs") (class "Default")
      (node (ref "CPLD1") (pin "20") (pinfunction "I/O_20") (pintype "bidirectional"))
      (node (ref "XC6") (pin "1") (pinfunction "CD/DAT3_1") (pintype "passive"))
    )
    (net (code "78") (name "/sd_dat") (class "Default")
      (node (ref "CPLD1") (pin "23") (pinfunction "I/O_23") (pintype "bidirectional"))
      (node (ref "XC6") (pin "7") (pinfunction "DAT0_7") (pintype "passive"))
    )
    (net (code "79") (name "/sd_det") (class "Default")
      (node (ref "CPLD1") (pin "36") (pinfunction "I/O,GTS1_36") (pintype "bidirectional"))
      (node (ref "XC6") (pin "10") (pinfunction "DET_SW_10") (pintype "passive"))
    )
    (net (code "80") (name "/sd_din") (class "Default")
      (node (ref "CPLD1") (pin "21") (pinfunction "I/O_21") (pintype "bidirectional"))
      (node (ref "XC6") (pin "2") (pinfunction "CMD_2") (pintype "passive"))
    )
    (net (code "81") (name "/sd_prot") (class "Default")
      (node (ref "CPLD1") (pin "19") (pinfunction "I/O_19") (pintype "bidirectional"))
      (node (ref "XC6") (pin "12") (pinfunction "PROT_SW_12") (pintype "passive"))
    )
    (net (code "82") (name "3V3") (class "Default")
      (node (ref "XC7") (pin "1") (pinfunction "1_1") (pintype "passive"))
    )
    (net (code "83") (name "5V") (class "Default")
      (node (ref "LED10") (pin "1") (pinfunction "A_1") (pintype "passive"))
      (node (ref "LED10") (pin "2") (pinfunction "A_2") (pintype "passive"))
      (node (ref "LED11") (pin "1") (pinfunction "A_1") (pintype "passive"))
      (node (ref "LED11") (pin "2") (pinfunction "A_2") (pintype "passive"))
      (node (ref "LED12") (pin "1") (pinfunction "A_1") (pintype "passive"))
      (node (ref "LED12") (pin "2") (pinfunction "A_2") (pintype "passive"))
      (node (ref "R137") (pin "2") (pinfunction "2_2") (pintype "passive"))
    )
    (net (code "84") (name "DVDD_FPGA") (class "Default")
      (node (ref "CPLD1") (pin "15") (pinfunction "VCCINT_3.3V_15") (pintype "power_in"))
      (node (ref "CPLD1") (pin "26") (pinfunction "VCCIO_2.5V/3.3V_26") (pintype "power_in"))
      (node (ref "CPLD1") (pin "35") (pinfunction "VCCINT_3.3V_35") (pintype "power_in"))
      (node (ref "FLASH1") (pin "3") (pinfunction "WP#_3") (pintype "passive"))
      (node (ref "FLASH1") (pin "7") (pinfunction "HOLD#_7") (pintype "passive"))
      (node (ref "FLASH1") (pin "8") (pinfunction "Vdd_8") (pintype "passive"))
      (node (ref "FPGA1") (pin "AB15") (pinfunction "CFGBVS_0_AB15") (pintype "input"))
      (node (ref "IC15") (pin "8") (pinfunction "VCC_8") (pintype "power_in"))
      (node (ref "IC16") (pin "5") (pinfunction "WDS_5") (pintype "input"))
      (node (ref "IC16") (pin "8") (pinfunction "VCC_8") (pintype "power_in"))
      (node (ref "R113") (pin "2") (pinfunction "2_2") (pintype "passive"))
      (node (ref "R114") (pin "2") (pinfunction "2_2") (pintype "passive"))
      (node (ref "R115") (pin "1") (pinfunction "1_1") (pintype "passive"))
      (node (ref "R116") (pin "1") (pinfunction "1_1") (pintype "passive"))
      (node (ref "R117") (pin "1") (pinfunction "1_1") (pintype "passive"))
      (node (ref "R124") (pin "1") (pinfunction "1_1") (pintype "passive"))
      (node (ref "R125") (pin "2") (pinfunction "2_2") (pintype "passive"))
      (node (ref "R126") (pin "1") (pinfunction "1_1") (pintype "passive"))
      (node (ref "R127") (pin "1") (pinfunction "1_1") (pintype "passive"))
      (node (ref "R128") (pin "2") (pinfunction "2_2") (pintype "passive"))
      (node (ref "R133") (pin "2") (pinfunction "2_2") (pintype "passive"))
      (node (ref "R140") (pin "2") (pinfunction "2_2") (pintype "passive"))
      (node (ref "R141") (pin "2") (pinfunction "2_2") (pintype "passive"))
      (node (ref "R142") (pin "2") (pinfunction "2_2") (pintype "passive"))
      (node (ref "R143") (pin "2") (pinfunction "2_2") (pintype "passive"))
      (node (ref "R232") (pin "1") (pinfunction "1_1") (pintype "passive"))
      (node (ref "R233") (pin "1") (pinfunction "1_1") (pintype "passive"))
      (node (ref "R234") (pin "1") (pinfunction "1_1") (pintype "passive"))
      (node (ref "XC5") (pin "2") (pinfunction "VREF_2") (pintype "passive"))
      (node (ref "XC6") (pin "11") (pinfunction "SWITCH_11") (pintype "passive"))
      (node (ref "XC6") (pin "4") (pinfunction "VDD_4") (pintype "passive"))
    )
    (net (code "85") (name "GND") (class "Default")
      (node (ref "C260") (pin "1") (pinfunction "1_1") (pintype "passive"))
      (node (ref "C261") (pin "2") (pinfunction "2_2") (pintype "passive"))
      (node (ref "C262") (pin "1") (pinfunction "1_1") (pintype "passive"))
      (node (ref "CPLD1") (pin "17") (pinfunction "GND_17") (pintype "power_in"))
      (node (ref "CPLD1") (pin "25") (pinfunction "GND_25") (pintype "power_in"))
      (node (ref "CPLD1") (pin "4") (pinfunction "GND_4") (pintype "power_in"))
      (node (ref "FLASH1") (pin "4") (pinfunction "Vss_4") (pintype "passive"))
      (node (ref "FPGA1") (pin "P15") (pinfunction "IO_L3P_T0_DQS_PUDC_B_14_P15") (pintype "bidirectional"))
      (node (ref "FPGA1") (pin "R11") (pinfunction "DXN_0_R11") (pintype "input"))
      (node (ref "FPGA1") (pin "R12") (pinfunction "DXP_0_R12") (pintype "input"))
      (node (ref "IC15") (pin "4") (pinfunction "VSS_4") (pintype "power_in"))
      (node (ref "IC15") (pin "7") (pinfunction "NC_7") (pintype "passive"))
      (node (ref "IC16") (pin "4") (pinfunction "VSS_4") (pintype "power_in"))
      (node (ref "Q10") (pin "2") (pinfunction "S_2") (pintype "passive"))
      (node (ref "Q11") (pin "2") (pinfunction "S_2") (pintype "passive"))
      (node (ref "Q12") (pin "2") (pinfunction "S_2") (pintype "passive"))
      (node (ref "Q13") (pin "2") (pinfunction "S_2") (pintype "passive"))
      (node (ref "Q7") (pin "2") (pinfunction "S_2") (pintype "passive"))
      (node (ref "Q8") (pin "2") (pinfunction "S_2") (pintype "passive"))
      (node (ref "Q9") (pin "2") (pinfunction "S_2") (pintype "passive"))
      (node (ref "R115") (pin "3") (pinfunction "3_3") (pintype "passive"))
      (node (ref "R116") (pin "3") (pinfunction "3_3") (pintype "passive"))
      (node (ref "R117") (pin "3") (pinfunction "3_3") (pintype "passive"))
      (node (ref "R129") (pin "1") (pinfunction "1_1") (pintype "passive"))
      (node (ref "R130") (pin "2") (pinfunction "2_2") (pintype "passive"))
      (node (ref "R222") (pin "2") (pinfunction "2_2") (pintype "passive"))
      (node (ref "R223") (pin "2") (pinfunction "2_2") (pintype "passive"))
      (node (ref "R224") (pin "2") (pinfunction "2_2") (pintype "passive"))
      (node (ref "R225") (pin "2") (pinfunction "2_2") (pintype "passive"))
      (node (ref "R226") (pin "2") (pinfunction "2_2") (pintype "passive"))
      (node (ref "R227") (pin "1") (pinfunction "1_1") (pintype "passive"))
      (node (ref "R232") (pin "3") (pinfunction "3_3") (pintype "passive"))
      (node (ref "R233") (pin "3") (pinfunction "3_3") (pintype "passive"))
      (node (ref "R234") (pin "3") (pinfunction "3_3") (pintype "passive"))
      (node (ref "S1") (pin "2") (pinfunction "2_2") (pintype "passive"))
      (node (ref "XC5") (pin "1") (pinfunction "GND_1") (pintype "passive"))
      (node (ref "XC5") (pin "11") (pinfunction "GND_11") (pintype "passive"))
      (node (ref "XC5") (pin "13") (pinfunction "GND_13") (pintype "passive"))
      (node (ref "XC5") (pin "3") (pinfunction "GND_3") (pintype "passive"))
      (node (ref "XC5") (pin "5") (pinfunction "GND_5") (pintype "passive"))
      (node (ref "XC5") (pin "7") (pinfunction "GND_7") (pintype "passive"))
      (node (ref "XC5") (pin "9") (pinfunction "GND_9") (pintype "passive"))
      (node (ref "XC6") (pin "0") (pinfunction "SHIELD_0") (pintype "passive"))
      (node (ref "XC6") (pin "3") (pinfunction "VSS_3") (pintype "passive"))
      (node (ref "XC6") (pin "6") (pinfunction "VSS_6") (pintype "passive"))
      (node (ref "XC7") (pin "4") (pinfunction "4_4") (pintype "passive"))
    )
    (net (code "86") (name "Net-(IC16-RSTin)") (class "Default")
      (node (ref "IC16") (pin "1") (pinfunction "RSTin_1") (pintype "input"))
      (node (ref "R128") (pin "1") (pinfunction "1_1") (pintype "passive"))
      (node (ref "R129") (pin "2") (pinfunction "2_2") (pintype "passive"))
    )
    (net (code "87") (name "Net-(IC16-SRT)") (class "Default")
      (node (ref "C262") (pin "2") (pinfunction "2_2") (pintype "passive"))
      (node (ref "IC16") (pin "3") (pinfunction "SRT_3") (pintype "passive"))
    )
    (net (code "88") (name "Net-(IC16-SWT)") (class "Default")
      (node (ref "C260") (pin "2") (pinfunction "2_2") (pintype "passive"))
      (node (ref "IC16") (pin "2") (pinfunction "SWT_2") (pintype "passive"))
    )
    (net (code "89") (name "Net-(LED7-A)") (class "Default")
      (node (ref "LED7") (pin "2") (pinfunction "A_2") (pintype "passive"))
      (node (ref "R113") (pin "1") (pinfunction "1_1") (pintype "passive"))
    )
    (net (code "90") (name "Net-(LED7-K)") (class "Default")
      (node (ref "CPLD1") (pin "8") (pinfunction "I/O_8") (pintype "bidirectional"))
      (node (ref "LED7") (pin "1") (pinfunction "K_1") (pintype "passive"))
    )
    (net (code "91") (name "Net-(LED8-A)") (class "Default")
      (node (ref "LED8") (pin "2") (pinfunction "A_2") (pintype "passive"))
      (node (ref "R114") (pin "1") (pinfunction "1_1") (pintype "passive"))
    )
    (net (code "92") (name "Net-(LED8-K)") (class "Default")
      (node (ref "CPLD1") (pin "7") (pinfunction "I/O_7") (pintype "bidirectional"))
      (node (ref "LED8") (pin "1") (pinfunction "K_1") (pintype "passive"))
    )
    (net (code "93") (name "Net-(LED9-A)") (class "Default")
      (node (ref "LED9") (pin "2") (pinfunction "A_2") (pintype "passive"))
      (node (ref "R137") (pin "1") (pinfunction "1_1") (pintype "passive"))
    )
    (net (code "94") (name "Net-(LED9-K)") (class "Default")
      (node (ref "LED9") (pin "1") (pinfunction "K_1") (pintype "passive"))
      (node (ref "Q13") (pin "3") (pinfunction "D_3") (pintype "passive"))
    )
    (net (code "95") (name "Net-(LED10-K-Pad3)") (class "Default")
      (node (ref "LED10") (pin "3") (pinfunction "K_3") (pintype "passive"))
      (node (ref "R148") (pin "2") (pinfunction "2_2") (pintype "passive"))
    )
    (net (code "96") (name "Net-(LED10-K-Pad4)") (class "Default")
      (node (ref "LED10") (pin "4") (pinfunction "K_4") (pintype "passive"))
      (node (ref "R149") (pin "1") (pinfunction "1_1") (pintype "passive"))
    )
    (net (code "97") (name "Net-(LED11-K-Pad3)") (class "Default")
      (node (ref "LED11") (pin "3") (pinfunction "K_3") (pintype "passive"))
      (node (ref "R146") (pin "2") (pinfunction "2_2") (pintype "passive"))
    )
    (net (code "98") (name "Net-(LED11-K-Pad4)") (class "Default")
      (node (ref "LED11") (pin "4") (pinfunction "K_4") (pintype "passive"))
      (node (ref "R147") (pin "2") (pinfunction "2_2") (pintype "passive"))
    )
    (net (code "99") (name "Net-(LED12-K-Pad3)") (class "Default")
      (node (ref "LED12") (pin "3") (pinfunction "K_3") (pintype "passive"))
      (node (ref "R145") (pin "1") (pinfunction "1_1") (pintype "passive"))
    )
    (net (code "100") (name "Net-(LED12-K-Pad4)") (class "Default")
      (node (ref "LED12") (pin "4") (pinfunction "K_4") (pintype "passive"))
      (node (ref "R144") (pin "1") (pinfunction "1_1") (pintype "passive"))
    )
    (net (code "101") (name "Net-(Q7-D)") (class "Default")
      (node (ref "Q7") (pin "3") (pinfunction "D_3") (pintype "passive"))
      (node (ref "R144") (pin "2") (pinfunction "2_2") (pintype "passive"))
    )
    (net (code "102") (name "Net-(Q8-D)") (class "Default")
      (node (ref "Q8") (pin "3") (pinfunction "D_3") (pintype "passive"))
      (node (ref "R145") (pin "2") (pinfunction "2_2") (pintype "passive"))
    )
    (net (code "103") (name "Net-(Q9-D)") (class "Default")
      (node (ref "Q9") (pin "3") (pinfunction "D_3") (pintype "passive"))
      (node (ref "R149") (pin "2") (pinfunction "2_2") (pintype "passive"))
    )
    (net (code "104") (name "Net-(Q10-D)") (class "Default")
      (node (ref "Q10") (pin "3") (pinfunction "D_3") (pintype "passive"))
      (node (ref "R148") (pin "1") (pinfunction "1_1") (pintype "passive"))
    )
    (net (code "105") (name "Net-(Q11-D)") (class "Default")
      (node (ref "Q11") (pin "3") (pinfunction "D_3") (pintype "passive"))
      (node (ref "R146") (pin "1") (pinfunction "1_1") (pintype "passive"))
    )
    (net (code "106") (name "Net-(Q12-D)") (class "Default")
      (node (ref "Q12") (pin "3") (pinfunction "D_3") (pintype "passive"))
      (node (ref "R147") (pin "1") (pinfunction "1_1") (pintype "passive"))
    )
    (net (code "107") (name "Net-(R135-Pad2)") (class "Default")
      (node (ref "R135") (pin "2") (pinfunction "2_2") (pintype "passive"))
      (node (ref "XC7") (pin "2") (pinfunction "2_2") (pintype "passive"))
    )
    (net (code "108") (name "Net-(R136-Pad2)") (class "Default")
      (node (ref "R136") (pin "2") (pinfunction "2_2") (pintype "passive"))
      (node (ref "XC7") (pin "3") (pinfunction "3_3") (pintype "passive"))
    )
    (net (code "109") (name "unconnected-(CPLD1D-I{slash}O-Pad27)") (class "Default")
      (node (ref "CPLD1") (pin "27") (pinfunction "I/O_27") (pintype "bidirectional"))
    )
    (net (code "110") (name "unconnected-(CPLD1D-I{slash}O-Pad28)") (class "Default")
      (node (ref "CPLD1") (pin "28") (pinfunction "I/O_28") (pintype "bidirectional"))
    )
    (net (code "111") (name "unconnected-(FPGA1C-IO_L7N_T1_D10_14-PadK26)") (class "Default")
      (node (ref "FPGA1") (pin "K26") (pinfunction "IO_L7N_T1_D10_14_K26") (pintype "bidirectional"))
    )
    (net (code "112") (name "unconnected-(FPGA1C-IO_L7P_T1_D09_14-PadK25)") (class "Default")
      (node (ref "FPGA1") (pin "K25") (pinfunction "IO_L7P_T1_D09_14_K25") (pintype "bidirectional"))
    )
    (net (code "113") (name "unconnected-(FPGA1C-IO_L10N_T1_D15_14-PadM25)") (class "Default")
      (node (ref "FPGA1") (pin "M25") (pinfunction "IO_L10N_T1_D15_14_M25") (pintype "bidirectional+no_connect"))
    )
    (net (code "114") (name "unconnected-(FPGA1C-IO_L12N_T1_MRCC_14-PadM22)") (class "Default")
      (node (ref "FPGA1") (pin "M22") (pinfunction "IO_L12N_T1_MRCC_14_M22") (pintype "bidirectional"))
    )
    (net (code "115") (name "unconnected-(FPGA1C-IO_L12P_T1_MRCC_14-PadM21)") (class "Default")
      (node (ref "FPGA1") (pin "M21") (pinfunction "IO_L12P_T1_MRCC_14_M21") (pintype "bidirectional"))
    )
    (net (code "116") (name "unconnected-(FPGA1C-IO_L17N_T2_A13_D29_14-PadP24)") (class "Default")
      (node (ref "FPGA1") (pin "P24") (pinfunction "IO_L17N_T2_A13_D29_14_P24") (pintype "bidirectional"))
    )
    (net (code "117") (name "unconnected-(FPGA1C-IO_L17P_T2_A14_D30_14-PadP23)") (class "Default")
      (node (ref "FPGA1") (pin "P23") (pinfunction "IO_L17P_T2_A14_D30_14_P23") (pintype "bidirectional"))
    )
    (net (code "118") (name "unconnected-(FPGA1C-IO_L20N_T3_A07_D23_14-PadM26)") (class "Default")
      (node (ref "FPGA1") (pin "M26") (pinfunction "IO_L20N_T3_A07_D23_14_M26") (pintype "bidirectional"))
    )
    (net (code "119") (name "unconnected-(FPGA1C-IO_L20P_T3_A08_D24_14-PadN26)") (class "Default")
      (node (ref "FPGA1") (pin "N26") (pinfunction "IO_L20P_T3_A08_D24_14_N26") (pintype "bidirectional"))
    )
    (net (code "120") (name "unconnected-(FPGA1C-IO_L21N_T3_DQS_A06_D22_14-PadT25)") (class "Default")
      (node (ref "FPGA1") (pin "T25") (pinfunction "IO_L21N_T3_DQS_A06_D22_14_T25") (pintype "bidirectional"))
    )
    (net (code "121") (name "unconnected-(FPGA1C-IO_L21P_T3_DQS_14-PadT24)") (class "Default")
      (node (ref "FPGA1") (pin "T24") (pinfunction "IO_L21P_T3_DQS_14_T24") (pintype "bidirectional"))
    )
    (net (code "122") (name "unconnected-(FPGA1C-IO_L23N_T3_A02_D18_14-PadR22)") (class "Default")
      (node (ref "FPGA1") (pin "R22") (pinfunction "IO_L23N_T3_A02_D18_14_R22") (pintype "bidirectional"))
    )
    (net (code "123") (name "unconnected-(FPGA1C-IO_L23P_T3_A03_D19_14-PadT22)") (class "Default")
      (node (ref "FPGA1") (pin "T22") (pinfunction "IO_L23P_T3_A03_D19_14_T22") (pintype "bidirectional+no_connect"))
    )
    (net (code "124") (name "unconnected-(FPGA1C-IO_L24N_T3_A00_D16_14-PadR23)") (class "Default")
      (node (ref "FPGA1") (pin "R23") (pinfunction "IO_L24N_T3_A00_D16_14_R23") (pintype "bidirectional"))
    )
    (net (code "125") (name "unconnected-(FPGA1C-IO_L24P_T3_A01_D17_14-PadT23)") (class "Default")
      (node (ref "FPGA1") (pin "T23") (pinfunction "IO_L24P_T3_A01_D17_14_T23") (pintype "bidirectional"))
    )
    (net (code "126") (name "unconnected-(XC5-NC-Pad12)") (class "Default")
      (node (ref "XC5") (pin "12") (pinfunction "NC_12") (pintype "passive"))
    )
    (net (code "127") (name "unconnected-(XC5-SRST-Pad14)") (class "Default")
      (node (ref "XC5") (pin "14") (pinfunction "SRST_14") (pintype "passive"))
    )
    (net (code "128") (name "unconnected-(XC6-DAT1-Pad8)") (class "Default")
      (node (ref "XC6") (pin "8") (pinfunction "DAT1_8") (pintype "passive"))
    )
    (net (code "129") (name "unconnected-(XC6-DAT2-Pad9)") (class "Default")
      (node (ref "XC6") (pin "9") (pinfunction "DAT2_9") (pintype "passive"))
    )
  )
)
